# esp_teleinfo.net
KiCad netlist of a schematic drawn in EasyEDA
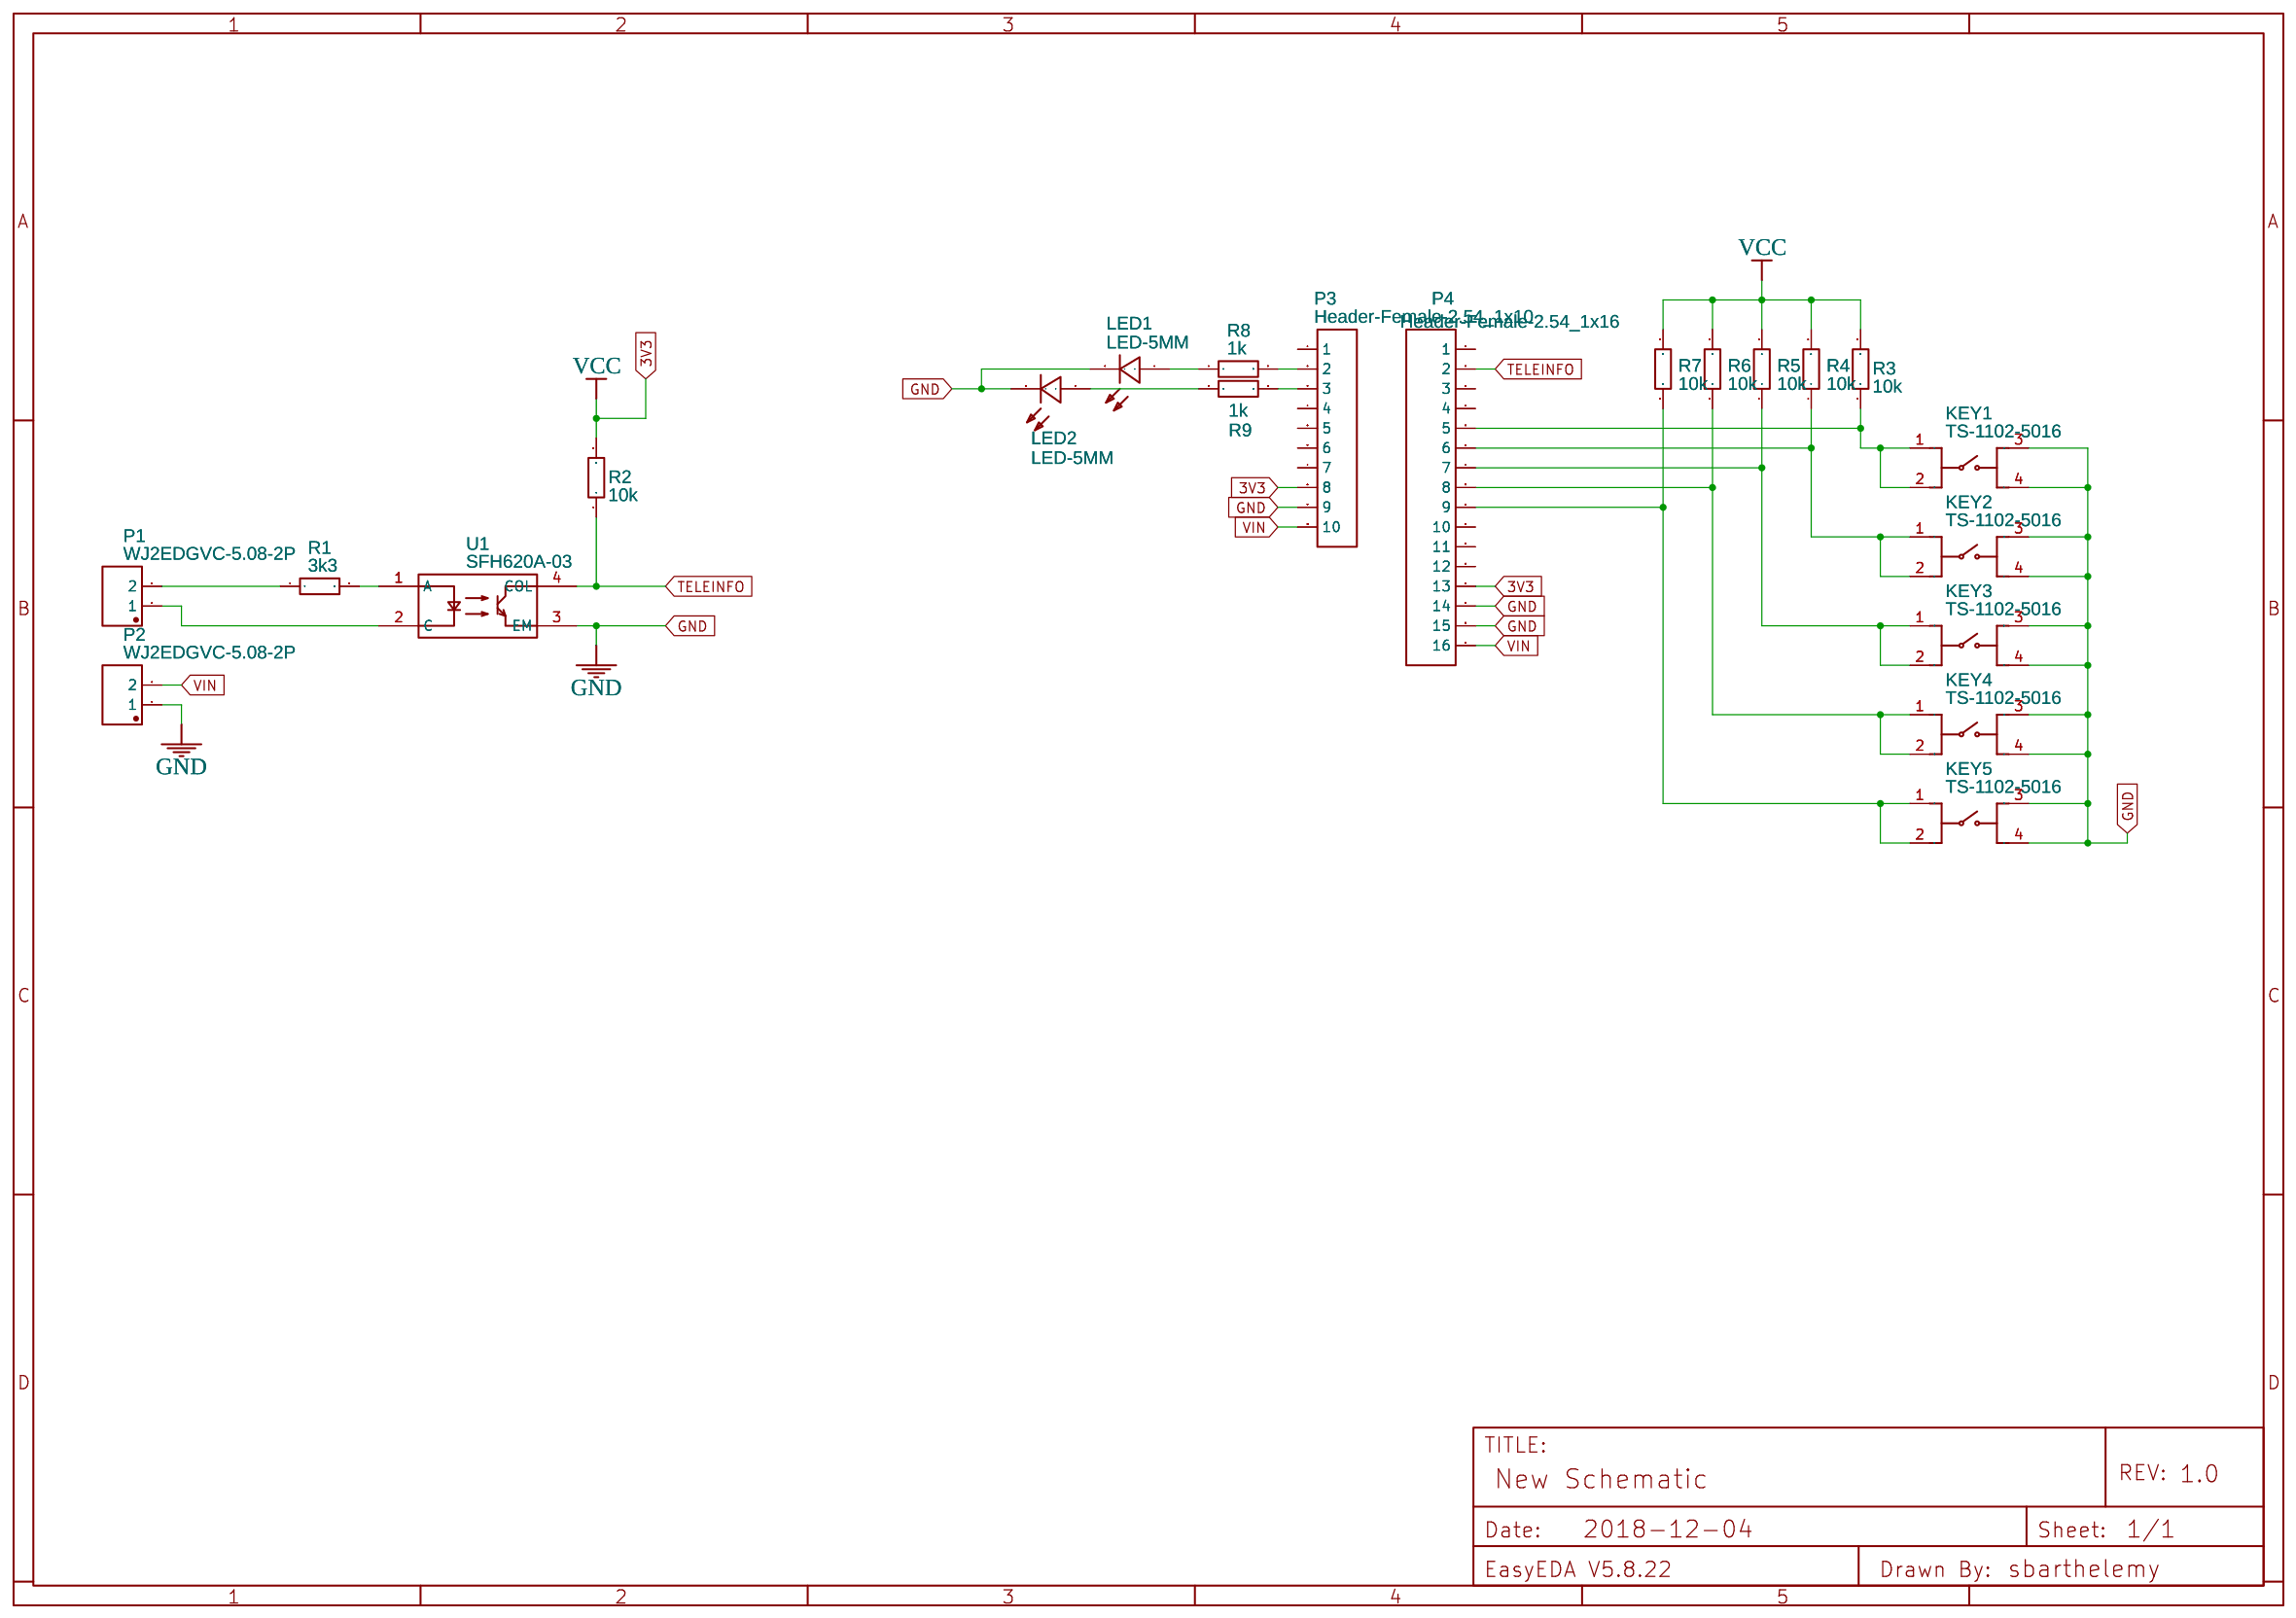
[diagram p0: schematic sheet]

(export (version "E")
  (design (tool "Eeschema 10.0.6"))
  (components
    (comp (ref "KEY1")
      (value "TS-1102-5016")
      (fields (field (name "BOM_Supplier Part") "C111609"))
      (libsource (lib "") (part "Unknown_990_230"))
    )
    (comp (ref "KEY2")
      (value "TS-1102-5016")
      (fields (field (name "BOM_Supplier Part") "C111609"))
      (libsource (lib "") (part "Unknown_990_275"))
    )
    (comp (ref "KEY3")
      (value "TS-1102-5016")
      (fields (field (name "BOM_Supplier Part") "C111609"))
      (libsource (lib "") (part "Unknown_990_320"))
    )
    (comp (ref "KEY4")
      (value "TS-1102-5016")
      (fields (field (name "BOM_Supplier Part") "C111609"))
      (libsource (lib "") (part "Unknown_990_365"))
    )
    (comp (ref "KEY5")
      (value "TS-1102-5016")
      (fields (field (name "BOM_Supplier Part") "C111609"))
      (libsource (lib "") (part "Unknown_990_410"))
    )
    (comp (ref "LED1")
      (value "LED-5MM")
      (fields (field (name "BOM_Manufacturer Part") "5AR2ST10") (field (name "BOM_Supplier Part") "C52721"))
      (libsource (lib "") (part "Unknown_565_180"))
    )
    (comp (ref "LED2")
      (value "LED-5MM")
      (fields (field (name "BOM_Manufacturer Part") "5AR2ST10") (field (name "BOM_Supplier Part") "C52721"))
      (libsource (lib "") (part "Unknown_525_190"))
    )
    (comp (ref "P1")
      (value "WJ2EDGVC-5.08-2P")
      (fields (field (name "BOM_Supplier Part") "C8445"))
      (libsource (lib "") (part "Unknown_60_295"))
    )
    (comp (ref "P2")
      (value "WJ2EDGVC-5.08-2P")
      (fields (field (name "BOM_Supplier Part") "C8445"))
      (libsource (lib "") (part "Unknown_60_345"))
    )
    (comp (ref "P3")
      (value "Header-Female-2.54_1x10")
      (fields
        (field (name "BOM_Manufacturer Part") "2.54mm 1*10P Straight Female header Gold-plated")
        (field (name "BOM_Supplier Part") "C35445")
      )
      (libsource (lib "") (part "Unknown_665_215"))
    )
    (comp (ref "P4")
      (value "Header-Female-2.54_1x16")
      (fields
        (field (name "BOM_Manufacturer Part") "Female header1*16P pitch 2.54mm")
        (field (name "BOM_Supplier Part") "C66987")
      )
      (libsource (lib "") (part "Unknown_720_245"))
    )
    (comp (ref "R1")
      (value "3k3")
      (fields (field (name "BOM_Manufacturer Part") "?"))
      (libsource (lib "") (part "Res_AXIAL-0.3(1/8W)_EU_1"))
    )
    (comp (ref "R2")
      (value "10k")
      (fields (field (name "BOM_Manufacturer Part") "?"))
      (libsource (lib "") (part "Res_AXIAL-0.3(1/8W)_EU"))
    )
    (comp (ref "R3")
      (value "10k")
      (fields (field (name "BOM_Manufacturer Part") "?"))
      (libsource (lib "") (part "Res_AXIAL-0.3(1/8W)_EU"))
    )
    (comp (ref "R4")
      (value "10k")
      (fields (field (name "BOM_Manufacturer Part") "?"))
      (libsource (lib "") (part "Res_AXIAL-0.3(1/8W)_EU"))
    )
    (comp (ref "R5")
      (value "10k")
      (fields (field (name "BOM_Manufacturer Part") "?"))
      (libsource (lib "") (part "Res_AXIAL-0.3(1/8W)_EU"))
    )
    (comp (ref "R6")
      (value "10k")
      (fields (field (name "BOM_Manufacturer Part") "?"))
      (libsource (lib "") (part "Res_AXIAL-0.3(1/8W)_EU"))
    )
    (comp (ref "R7")
      (value "10k")
      (fields (field (name "BOM_Manufacturer Part") "?"))
      (libsource (lib "") (part "Res_AXIAL-0.3(1/8W)_EU"))
    )
    (comp (ref "R8")
      (value "1k")
      (fields (field (name "BOM_Manufacturer Part") "?"))
      (libsource (lib "") (part "Res_AXIAL-0.3(1/8W)_EU_1"))
    )
    (comp (ref "R9")
      (value "1k")
      (fields (field (name "BOM_Manufacturer Part") "?"))
      (libsource (lib "") (part "Res_AXIAL-0.3(1/8W)_EU_1"))
    )
    (comp (ref "U1")
      (value "SFH620A-03")
      (fields
        (field (name "BOM_Manufacturer Part") "SFH617A-4X016")
        (field (name "BOM_Supplier Part") "C145216")
      )
      (libsource (lib "") (part "Unknown_235_300"))
    )
  )
  (nets
    (net (code "1") (name "3V3") (class "Default")
      (node (ref "P3") (pin "8") (pinfunction "8_8") (pintype "input"))
      (node (ref "P4") (pin "13") (pinfunction "13_13") (pintype "input"))
      (node (ref "R2") (pin "2") (pinfunction "2_2") (pintype "unspecified"))
      (node (ref "R3") (pin "2") (pinfunction "2_2") (pintype "unspecified"))
      (node (ref "R4") (pin "2") (pinfunction "2_2") (pintype "unspecified"))
      (node (ref "R5") (pin "2") (pinfunction "2_2") (pintype "unspecified"))
      (node (ref "R6") (pin "2") (pinfunction "2_2") (pintype "unspecified"))
      (node (ref "R7") (pin "2") (pinfunction "2_2") (pintype "unspecified"))
    )
    (net (code "2") (name "GND") (class "Default")
      (node (ref "KEY1") (pin "3") (pinfunction "3_3") (pintype "unspecified"))
      (node (ref "KEY1") (pin "4") (pinfunction "4_4") (pintype "unspecified"))
      (node (ref "KEY2") (pin "3") (pinfunction "3_3") (pintype "unspecified"))
      (node (ref "KEY2") (pin "4") (pinfunction "4_4") (pintype "unspecified"))
      (node (ref "KEY3") (pin "3") (pinfunction "3_3") (pintype "unspecified"))
      (node (ref "KEY3") (pin "4") (pinfunction "4_4") (pintype "unspecified"))
      (node (ref "KEY4") (pin "3") (pinfunction "3_3") (pintype "unspecified"))
      (node (ref "KEY4") (pin "4") (pinfunction "4_4") (pintype "unspecified"))
      (node (ref "KEY5") (pin "3") (pinfunction "3_3") (pintype "unspecified"))
      (node (ref "KEY5") (pin "4") (pinfunction "4_4") (pintype "unspecified"))
      (node (ref "LED1") (pin "2") (pinfunction "-_2") (pintype "unspecified"))
      (node (ref "LED2") (pin "2") (pinfunction "-_2") (pintype "unspecified"))
      (node (ref "P2") (pin "1") (pinfunction "1_1") (pintype "unspecified"))
      (node (ref "P3") (pin "9") (pinfunction "9_9") (pintype "input"))
      (node (ref "P4") (pin "14") (pinfunction "14_14") (pintype "input"))
      (node (ref "P4") (pin "15") (pinfunction "15_15") (pintype "input"))
      (node (ref "U1") (pin "3") (pinfunction "EM_3") (pintype "unspecified"))
    )
    (net (code "3") (name "Net-(KEY1-Pad1)") (class "Default")
      (node (ref "KEY1") (pin "1") (pinfunction "1_1") (pintype "unspecified"))
      (node (ref "KEY1") (pin "2") (pinfunction "2_2") (pintype "unspecified"))
      (node (ref "P4") (pin "5") (pinfunction "5_5") (pintype "input"))
      (node (ref "R3") (pin "1") (pinfunction "1_1") (pintype "unspecified"))
    )
    (net (code "4") (name "Net-(KEY2-Pad1)") (class "Default")
      (node (ref "KEY2") (pin "1") (pinfunction "1_1") (pintype "unspecified"))
      (node (ref "KEY2") (pin "2") (pinfunction "2_2") (pintype "unspecified"))
      (node (ref "P4") (pin "6") (pinfunction "6_6") (pintype "input"))
      (node (ref "R4") (pin "1") (pinfunction "1_1") (pintype "unspecified"))
    )
    (net (code "5") (name "Net-(KEY3-Pad1)") (class "Default")
      (node (ref "KEY3") (pin "1") (pinfunction "1_1") (pintype "unspecified"))
      (node (ref "KEY3") (pin "2") (pinfunction "2_2") (pintype "unspecified"))
      (node (ref "P4") (pin "7") (pinfunction "7_7") (pintype "input"))
      (node (ref "R5") (pin "1") (pinfunction "1_1") (pintype "unspecified"))
    )
    (net (code "6") (name "Net-(KEY4-Pad1)") (class "Default")
      (node (ref "KEY4") (pin "1") (pinfunction "1_1") (pintype "unspecified"))
      (node (ref "KEY4") (pin "2") (pinfunction "2_2") (pintype "unspecified"))
      (node (ref "P4") (pin "8") (pinfunction "8_8") (pintype "input"))
      (node (ref "R6") (pin "1") (pinfunction "1_1") (pintype "unspecified"))
    )
    (net (code "7") (name "Net-(KEY5-Pad1)") (class "Default")
      (node (ref "KEY5") (pin "1") (pinfunction "1_1") (pintype "unspecified"))
      (node (ref "KEY5") (pin "2") (pinfunction "2_2") (pintype "unspecified"))
      (node (ref "P4") (pin "9") (pinfunction "9_9") (pintype "input"))
      (node (ref "R7") (pin "1") (pinfunction "1_1") (pintype "unspecified"))
    )
    (net (code "8") (name "Net-(LED1-+)") (class "Default")
      (node (ref "LED1") (pin "1") (pinfunction "+_1") (pintype "unspecified"))
      (node (ref "R8") (pin "1") (pinfunction "1_1") (pintype "unspecified"))
    )
    (net (code "9") (name "Net-(LED2-+)") (class "Default")
      (node (ref "LED2") (pin "1") (pinfunction "+_1") (pintype "unspecified"))
      (node (ref "R9") (pin "1") (pinfunction "1_1") (pintype "unspecified"))
    )
    (net (code "10") (name "Net-(P1-Pad2)") (class "Default")
      (node (ref "P1") (pin "2") (pinfunction "2_2") (pintype "unspecified"))
      (node (ref "R1") (pin "1") (pinfunction "1_1") (pintype "unspecified"))
    )
    (net (code "11") (name "Net-(P3-Pad2)") (class "Default")
      (node (ref "P3") (pin "2") (pinfunction "2_2") (pintype "input"))
      (node (ref "R8") (pin "2") (pinfunction "2_2") (pintype "unspecified"))
    )
    (net (code "12") (name "Net-(P3-Pad3)") (class "Default")
      (node (ref "P3") (pin "3") (pinfunction "3_3") (pintype "input"))
      (node (ref "R9") (pin "2") (pinfunction "2_2") (pintype "unspecified"))
    )
    (net (code "13") (name "Net-(U1-A)") (class "Default")
      (node (ref "R1") (pin "2") (pinfunction "2_2") (pintype "unspecified"))
      (node (ref "U1") (pin "1") (pinfunction "A_1") (pintype "unspecified"))
    )
    (net (code "14") (name "Net-(U1-C)") (class "Default")
      (node (ref "P1") (pin "1") (pinfunction "1_1") (pintype "unspecified"))
      (node (ref "U1") (pin "2") (pinfunction "C_2") (pintype "unspecified"))
    )
    (net (code "15") (name "TELEINFO") (class "Default")
      (node (ref "P4") (pin "2") (pinfunction "2_2") (pintype "input"))
      (node (ref "R2") (pin "1") (pinfunction "1_1") (pintype "unspecified"))
      (node (ref "U1") (pin "4") (pinfunction "COL_4") (pintype "unspecified"))
    )
    (net (code "16") (name "VIN") (class "Default")
      (node (ref "P2") (pin "2") (pinfunction "2_2") (pintype "unspecified"))
      (node (ref "P3") (pin "10") (pinfunction "10_10") (pintype "input"))
      (node (ref "P4") (pin "16") (pinfunction "16_16") (pintype "input"))
    )
    (net (code "17") (name "unconnected-(P3-Pad1)") (class "Default")
      (node (ref "P3") (pin "1") (pinfunction "1_1") (pintype "input"))
    )
    (net (code "18") (name "unconnected-(P3-Pad4)") (class "Default")
      (node (ref "P3") (pin "4") (pinfunction "4_4") (pintype "input"))
    )
    (net (code "19") (name "unconnected-(P3-Pad5)") (class "Default")
      (node (ref "P3") (pin "5") (pinfunction "5_5") (pintype "input"))
    )
    (net (code "20") (name "unconnected-(P3-Pad6)") (class "Default")
      (node (ref "P3") (pin "6") (pinfunction "6_6") (pintype "input"))
    )
    (net (code "21") (name "unconnected-(P3-Pad7)") (class "Default")
      (node (ref "P3") (pin "7") (pinfunction "7_7") (pintype "input"))
    )
    (net (code "22") (name "unconnected-(P4-Pad1)") (class "Default")
      (node (ref "P4") (pin "1") (pinfunction "1_1") (pintype "input"))
    )
    (net (code "23") (name "unconnected-(P4-Pad3)") (class "Default")
      (node (ref "P4") (pin "3") (pinfunction "3_3") (pintype "input"))
    )
    (net (code "24") (name "unconnected-(P4-Pad4)") (class "Default")
      (node (ref "P4") (pin "4") (pinfunction "4_4") (pintype "input"))
    )
    (net (code "25") (name "unconnected-(P4-Pad10)") (class "Default")
      (node (ref "P4") (pin "10") (pinfunction "10_10") (pintype "input"))
    )
    (net (code "26") (name "unconnected-(P4-Pad11)") (class "Default")
      (node (ref "P4") (pin "11") (pinfunction "11_11") (pintype "input"))
    )
    (net (code "27") (name "unconnected-(P4-Pad12)") (class "Default")
      (node (ref "P4") (pin "12") (pinfunction "12_12") (pintype "input"))
    )
  )
)
